# TALON_SRX_v1_4.net
KiCad netlist of a schematic drawn in EAGLE
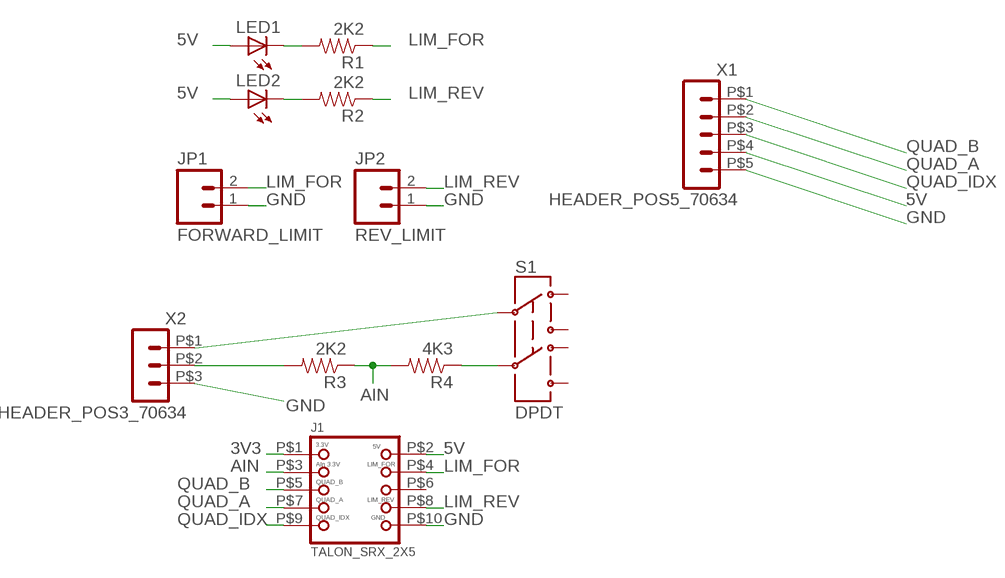
[diagram p0: schematic, sheet 1]

(export (version "E")
  (design (tool "Eeschema 10.0.6"))
  (components
    (comp (ref "J1")
      (value "TALON_SRX_2X5")
      (footprint "eagle-import:2X5-0.05-HEADER")
      (libsource (lib "eagle-import") (part "TALON_SRX_2X5"))
    )
    (comp (ref "JP1")
      (value "FORWARD_LIMIT")
      (footprint "eagle-import:MOLEX-1X2")
      (libsource (lib "eagle-import") (part "M02POLAR"))
    )
    (comp (ref "JP2")
      (value "REV_LIMIT")
      (footprint "eagle-import:MOLEX-1X2")
      (libsource (lib "eagle-import") (part "M02POLAR"))
    )
    (comp (ref "LED1")
      (value "LEDCHIP-LED0805")
      (footprint "eagle-import:CHIP-LED0805")
      (libsource (lib "eagle-import") (part "LEDCHIP-LED0805"))
    )
    (comp (ref "LED2")
      (value "LEDCHIP-LED0805")
      (footprint "eagle-import:CHIP-LED0805")
      (libsource (lib "eagle-import") (part "LEDCHIP-LED0805"))
    )
    (comp (ref "R1")
      (value "2K2")
      (footprint "eagle-import:0805")
      (libsource (lib "eagle-import") (part "RESISTOR0805-RES"))
    )
    (comp (ref "R2")
      (value "2K2")
      (footprint "eagle-import:0805")
      (libsource (lib "eagle-import") (part "RESISTOR0805-RES"))
    )
    (comp (ref "R3")
      (value "2K2")
      (footprint "eagle-import:0805")
      (libsource (lib "eagle-import") (part "RESISTOR0805-RES"))
    )
    (comp (ref "R4")
      (value "4K3")
      (footprint "eagle-import:0805")
      (libsource (lib "eagle-import") (part "RESISTOR0805-RES"))
    )
    (comp (ref "S1")
      (value "DPDT")
      (footprint "eagle-import:AYZ0202")
      (libsource (lib "eagle-import") (part "SWITCH-DPDTAYZ0202"))
    )
    (comp (ref "X1")
      (value "HEADER_POS5_70634")
      (footprint "eagle-import:70634-POS5")
      (libsource (lib "eagle-import") (part "HEADER_POS5_?70634"))
    )
    (comp (ref "X2")
      (value "HEADER_POS3_70634")
      (footprint "eagle-import:70634-POS3")
      (libsource (lib "eagle-import") (part "HEADER_POS3_?70634"))
    )
  )
  (nets
    (net (code "1") (name "/3V3") (class "Default")
      (node (ref "J1") (pin "P$1") (pinfunction "1_P$1") (pintype "passive"))
    )
    (net (code "2") (name "/5V") (class "Default")
      (node (ref "J1") (pin "P$2") (pinfunction "2_P$2") (pintype "passive"))
      (node (ref "LED1") (pin "A") (pinfunction "A_A") (pintype "passive"))
      (node (ref "LED2") (pin "A") (pinfunction "A_A") (pintype "passive"))
      (node (ref "X1") (pin "P$4") (pinfunction "4_P$4") (pintype "passive"))
    )
    (net (code "3") (name "/AIN") (class "Default")
      (node (ref "J1") (pin "P$3") (pinfunction "3_P$3") (pintype "passive"))
      (node (ref "R3") (pin "1") (pinfunction "1_1") (pintype "passive"))
      (node (ref "R4") (pin "2") (pinfunction "2_2") (pintype "passive"))
    )
    (net (code "4") (name "/GND") (class "Default")
      (node (ref "J1") (pin "P$10") (pinfunction "10_P$10") (pintype "passive"))
      (node (ref "JP1") (pin "1") (pinfunction "1_1") (pintype "passive"))
      (node (ref "JP2") (pin "1") (pinfunction "1_1") (pintype "passive"))
      (node (ref "X1") (pin "P$5") (pinfunction "5_P$5") (pintype "passive"))
      (node (ref "X2") (pin "P$3") (pinfunction "3_P$3") (pintype "passive"))
    )
    (net (code "5") (name "/LIM_FOR") (class "Default")
      (node (ref "J1") (pin "P$4") (pinfunction "4_P$4") (pintype "passive"))
      (node (ref "JP1") (pin "2") (pinfunction "2_2") (pintype "passive"))
      (node (ref "R1") (pin "1") (pinfunction "1_1") (pintype "passive"))
    )
    (net (code "6") (name "/LIM_REV") (class "Default")
      (node (ref "J1") (pin "P$8") (pinfunction "8_P$8") (pintype "passive"))
      (node (ref "JP2") (pin "2") (pinfunction "2_2") (pintype "passive"))
      (node (ref "R2") (pin "1") (pinfunction "1_1") (pintype "passive"))
    )
    (net (code "7") (name "/QUAD_A") (class "Default")
      (node (ref "J1") (pin "P$7") (pinfunction "7_P$7") (pintype "passive"))
      (node (ref "X1") (pin "P$2") (pinfunction "2_P$2") (pintype "passive"))
    )
    (net (code "8") (name "/QUAD_B") (class "Default")
      (node (ref "J1") (pin "P$5") (pinfunction "5_P$5") (pintype "passive"))
      (node (ref "X1") (pin "P$1") (pinfunction "1_P$1") (pintype "passive"))
    )
    (net (code "9") (name "/QUAD_IDX") (class "Default")
      (node (ref "J1") (pin "P$9") (pinfunction "9_P$9") (pintype "passive"))
      (node (ref "X1") (pin "P$3") (pinfunction "3_P$3") (pintype "passive"))
    )
    (net (code "10") (name "Net-(LED1-PadC)") (class "Default")
      (node (ref "LED1") (pin "C") (pinfunction "C_C") (pintype "passive"))
      (node (ref "R1") (pin "2") (pinfunction "2_2") (pintype "passive"))
    )
    (net (code "11") (name "Net-(LED2-PadC)") (class "Default")
      (node (ref "LED2") (pin "C") (pinfunction "C_C") (pintype "passive"))
      (node (ref "R2") (pin "2") (pinfunction "2_2") (pintype "passive"))
    )
    (net (code "12") (name "Net-(R4-Pad1)") (class "Default")
      (node (ref "R4") (pin "1") (pinfunction "1_1") (pintype "passive"))
      (node (ref "S1") (pin "5") (pinfunction "5_5") (pintype "bidirectional"))
    )
    (net (code "13") (name "Net-(X2-1)") (class "Default")
      (node (ref "S1") (pin "2") (pinfunction "2_2") (pintype "bidirectional"))
      (node (ref "X2") (pin "P$1") (pinfunction "1_P$1") (pintype "passive"))
    )
    (net (code "14") (name "Net-(X2-2)") (class "Default")
      (node (ref "R3") (pin "2") (pinfunction "2_2") (pintype "passive"))
      (node (ref "X2") (pin "P$2") (pinfunction "2_P$2") (pintype "passive"))
    )
    (net (code "15") (name "unconnected-(J1-6-PadP$6)") (class "Default")
      (node (ref "J1") (pin "P$6") (pinfunction "6_P$6") (pintype "passive"))
    )
    (net (code "16") (name "unconnected-(S1-Pad1)") (class "Default")
      (node (ref "S1") (pin "1") (pinfunction "1_1") (pintype "bidirectional"))
    )
    (net (code "17") (name "unconnected-(S1-Pad3)") (class "Default")
      (node (ref "S1") (pin "3") (pinfunction "3_3") (pintype "bidirectional"))
    )
    (net (code "18") (name "unconnected-(S1-Pad4)") (class "Default")
      (node (ref "S1") (pin "4") (pinfunction "4_4") (pintype "bidirectional"))
    )
    (net (code "19") (name "unconnected-(S1-Pad6)") (class "Default")
      (node (ref "S1") (pin "6") (pinfunction "6_6") (pintype "bidirectional"))
    )
  )
)
